# old_motor_line.net
KiCad netlist of a schematic drawn in EAGLE
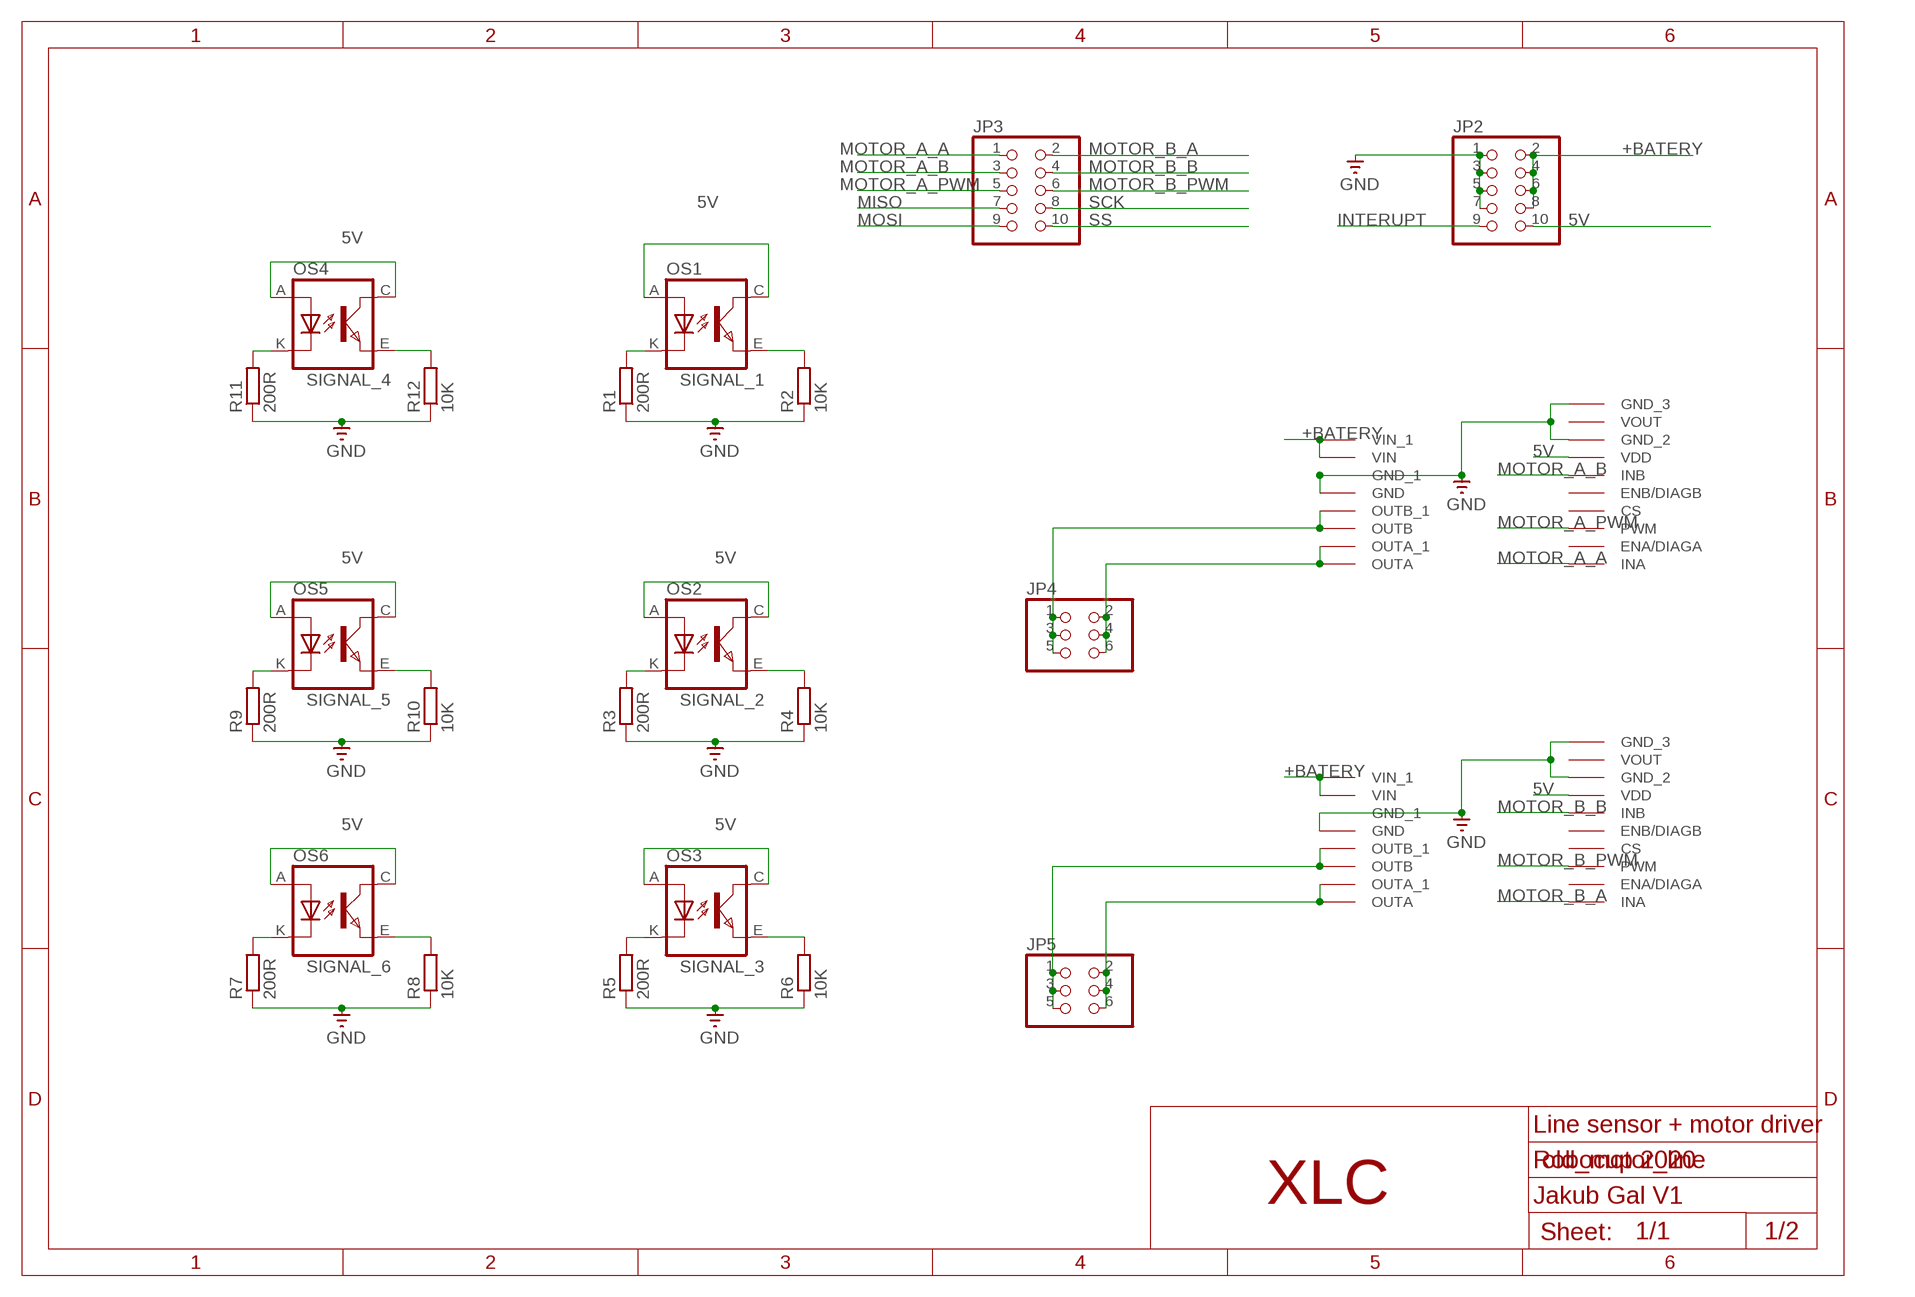
[diagram p0: schematic, sheet 1, part 1 of 2]
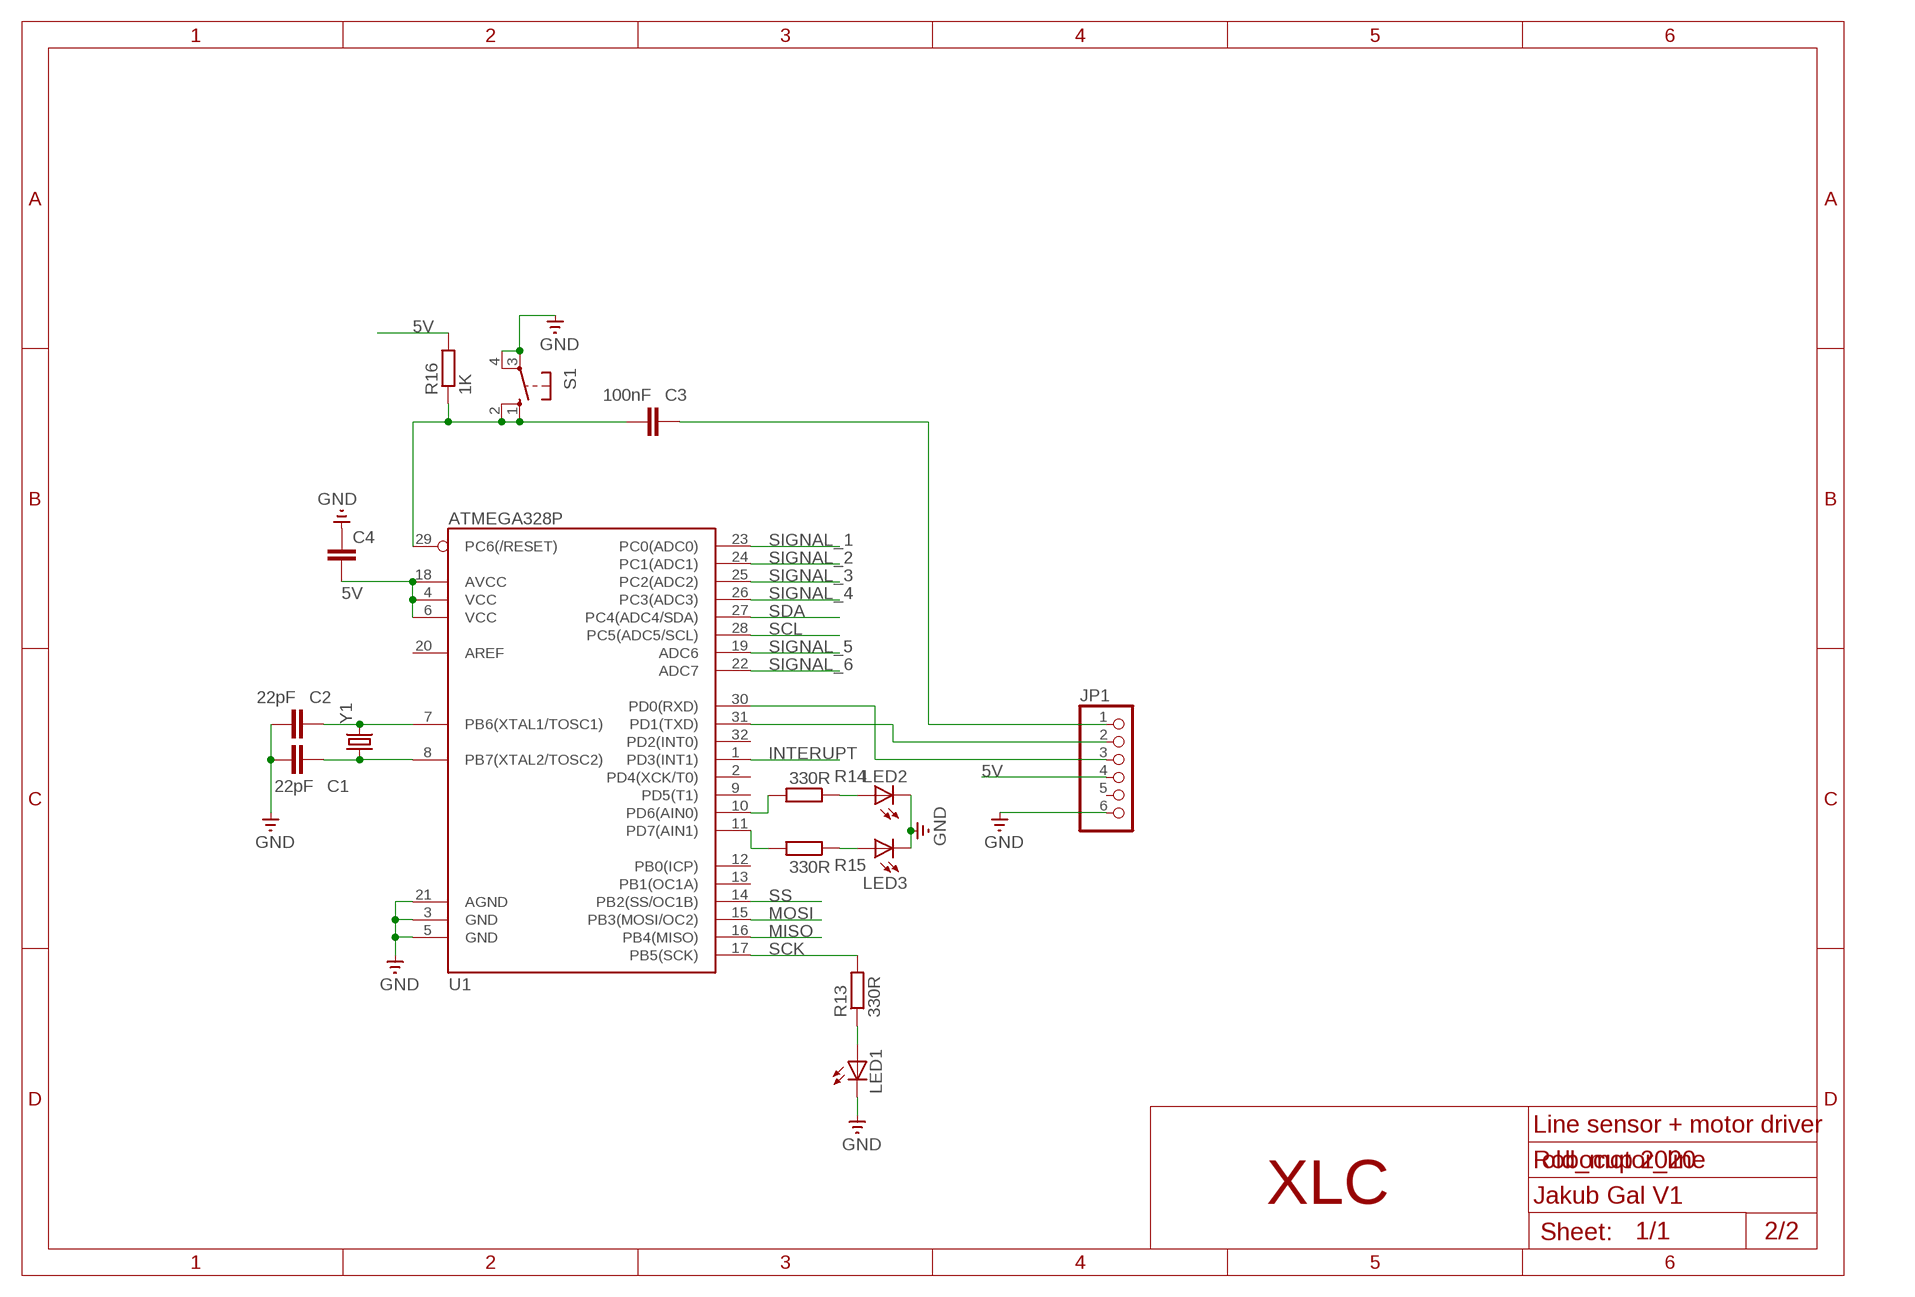
[diagram p1: schematic, sheet 1, part 2 of 2]

(export (version "E")
  (design (tool "Eeschema 10.0.6"))
  (components
    (comp (ref "C1")
      (value "22pF")
      (footprint "eagle-import:C0603")
      (libsource (lib "eagle-import") (part "rcl@1_C-EUC0603"))
    )
    (comp (ref "C2")
      (value "22pF")
      (footprint "eagle-import:C0603")
      (libsource (lib "eagle-import") (part "rcl@1_C-EUC0603"))
    )
    (comp (ref "C3")
      (value "100nF")
      (footprint "eagle-import:C0603")
      (libsource (lib "eagle-import") (part "rcl@1_C-EUC0603"))
    )
    (comp (ref "C4")
      (value "C-EUC0603")
      (footprint "eagle-import:C0603")
      (libsource (lib "eagle-import") (part "C-EUC0603"))
    )
    (comp (ref "JP1")
      (value "PINHD-1X6/90")
      (footprint "eagle-import:1X06_90")
      (libsource (lib "eagle-import") (part "PINHD-1X6/90"))
    )
    (comp (ref "JP2")
      (value "PINHD-2X5")
      (footprint "eagle-import:2X05")
      (libsource (lib "eagle-import") (part "PINHD-2X5"))
    )
    (comp (ref "JP3")
      (value "PINHD-2X5")
      (footprint "eagle-import:2X05")
      (libsource (lib "eagle-import") (part "PINHD-2X5"))
    )
    (comp (ref "JP4")
      (value "PINHD-2X3")
      (footprint "eagle-import:2X03")
      (libsource (lib "eagle-import") (part "PINHD-2X3"))
    )
    (comp (ref "JP5")
      (value "PINHD-2X3")
      (footprint "eagle-import:2X03")
      (libsource (lib "eagle-import") (part "PINHD-2X3"))
    )
    (comp (ref "LED1")
      (value "LEDCHIPLED_0603")
      (footprint "eagle-import:CHIPLED_0603")
      (libsource (lib "eagle-import") (part "LEDCHIPLED_0603"))
    )
    (comp (ref "LED2")
      (value "LEDCHIPLED_0603")
      (footprint "eagle-import:CHIPLED_0603")
      (libsource (lib "eagle-import") (part "LEDCHIPLED_0603"))
    )
    (comp (ref "LED3")
      (value "LEDCHIPLED_0603")
      (footprint "eagle-import:CHIPLED_0603")
      (libsource (lib "eagle-import") (part "LEDCHIPLED_0603"))
    )
    (comp (ref "OS1")
      (value "TCRT5000")
      (footprint "eagle-import:TCRT5000")
      (libsource (lib "eagle-import") (part "TCRT5000"))
    )
    (comp (ref "OS2")
      (value "TCRT5000")
      (footprint "eagle-import:TCRT5000")
      (libsource (lib "eagle-import") (part "TCRT5000"))
    )
    (comp (ref "OS3")
      (value "TCRT5000")
      (footprint "eagle-import:TCRT5000")
      (libsource (lib "eagle-import") (part "TCRT5000"))
    )
    (comp (ref "OS4")
      (value "TCRT5000")
      (footprint "eagle-import:TCRT5000")
      (fields (field (name "SPICEPREFIX") "O"))
      (libsource (lib "eagle-import") (part "TCRT5000"))
    )
    (comp (ref "OS5")
      (value "TCRT5000")
      (footprint "eagle-import:TCRT5000")
      (libsource (lib "eagle-import") (part "TCRT5000"))
    )
    (comp (ref "OS6")
      (value "TCRT5000")
      (footprint "eagle-import:TCRT5000")
      (fields (field (name "SPICEPREFIX") "O"))
      (libsource (lib "eagle-import") (part "TCRT5000"))
    )
    (comp (ref "R1")
      (value "200R")
      (footprint "eagle-import:R0603")
      (libsource (lib "eagle-import") (part "R-EU_R0603"))
    )
    (comp (ref "R2")
      (value "10K")
      (footprint "eagle-import:R0603")
      (libsource (lib "eagle-import") (part "R-EU_R0603"))
    )
    (comp (ref "R3")
      (value "200R")
      (footprint "eagle-import:R0603")
      (libsource (lib "eagle-import") (part "R-EU_R0603"))
    )
    (comp (ref "R4")
      (value "10K")
      (footprint "eagle-import:R0603")
      (libsource (lib "eagle-import") (part "R-EU_R0603"))
    )
    (comp (ref "R5")
      (value "200R")
      (footprint "eagle-import:R0603")
      (libsource (lib "eagle-import") (part "R-EU_R0603"))
    )
    (comp (ref "R6")
      (value "10K")
      (footprint "eagle-import:R0603")
      (libsource (lib "eagle-import") (part "R-EU_R0603"))
    )
    (comp (ref "R7")
      (value "200R")
      (footprint "eagle-import:R0603")
      (libsource (lib "eagle-import") (part "R-EU_R0603"))
    )
    (comp (ref "R8")
      (value "10K")
      (footprint "eagle-import:R0603")
      (libsource (lib "eagle-import") (part "R-EU_R0603"))
    )
    (comp (ref "R9")
      (value "200R")
      (footprint "eagle-import:R0603")
      (libsource (lib "eagle-import") (part "R-EU_R0603"))
    )
    (comp (ref "R10")
      (value "10K")
      (footprint "eagle-import:R0603")
      (libsource (lib "eagle-import") (part "R-EU_R0603"))
    )
    (comp (ref "R11")
      (value "200R")
      (footprint "eagle-import:R0603")
      (libsource (lib "eagle-import") (part "R-EU_R0603"))
    )
    (comp (ref "R12")
      (value "10K")
      (footprint "eagle-import:R0603")
      (libsource (lib "eagle-import") (part "R-EU_R0603"))
    )
    (comp (ref "R13")
      (value "330R")
      (footprint "eagle-import:R0603")
      (libsource (lib "eagle-import") (part "R-EU_R0603"))
    )
    (comp (ref "R14")
      (value "330R")
      (footprint "eagle-import:R0603")
      (libsource (lib "eagle-import") (part "R-EU_R0603"))
    )
    (comp (ref "R15")
      (value "330R")
      (footprint "eagle-import:R0603")
      (libsource (lib "eagle-import") (part "R-EU_R0603"))
    )
    (comp (ref "R16")
      (value "1K")
      (footprint "eagle-import:R0603")
      (libsource (lib "eagle-import") (part "R-EU_R0603"))
    )
    (comp (ref "S1")
      (value "10-XX")
      (footprint "eagle-import:B3F-10XX")
      (fields (field (name "MPN") "B3F-1000"))
      (libsource (lib "eagle-import") (part "10-XX"))
    )
    (comp (ref "U$1")
      (value "MOTOR_DRIVER")
      (footprint "eagle-import:MOTOR_DRIVER")
      (libsource (lib "eagle-import") (part "MOTOR_DRIVER"))
    )
    (comp (ref "U$2")
      (value "MOTOR_DRIVER")
      (footprint "eagle-import:MOTOR_DRIVER")
      (libsource (lib "eagle-import") (part "MOTOR_DRIVER"))
    )
    (comp (ref "U1")
      (value "ATMEGA328P")
      (footprint "eagle-import:TQFP32-08")
      (libsource (lib "eagle-import") (part "ATMEGA328_SMT"))
    )
    (comp (ref "Y1")
      (value "CRYSTALHC49US")
      (footprint "eagle-import:HC49US")
      (libsource (lib "eagle-import") (part "CRYSTALHC49US"))
    )
  )
  (nets
    (net (code "1") (name "/+BATERY") (class "Default")
      (node (ref "JP2") (pin "2") (pinfunction "2_2") (pintype "passive"))
      (node (ref "JP2") (pin "4") (pinfunction "4_4") (pintype "passive"))
      (node (ref "JP2") (pin "6") (pinfunction "6_6") (pintype "passive"))
      (node (ref "JP2") (pin "8") (pinfunction "8_8") (pintype "passive"))
      (node (ref "U$1") (pin "VIN") (pinfunction "VIN_VIN") (pintype "bidirectional"))
      (node (ref "U$1") (pin "VIN_1") (pinfunction "VIN_1_VIN_1") (pintype "bidirectional"))
      (node (ref "U$2") (pin "VIN") (pinfunction "VIN_VIN") (pintype "bidirectional"))
      (node (ref "U$2") (pin "VIN_1") (pinfunction "VIN_1_VIN_1") (pintype "bidirectional"))
    )
    (net (code "2") (name "/5V") (class "Default")
      (node (ref "C4") (pin "2") (pinfunction "2_2") (pintype "passive"))
      (node (ref "JP1") (pin "4") (pinfunction "4_4") (pintype "passive"))
      (node (ref "JP2") (pin "10") (pinfunction "10_10") (pintype "passive"))
      (node (ref "OS1") (pin "A") (pinfunction "ANODE_A") (pintype "passive"))
      (node (ref "OS1") (pin "C") (pinfunction "COLLECTOR_C") (pintype "passive"))
      (node (ref "OS2") (pin "A") (pinfunction "ANODE_A") (pintype "passive"))
      (node (ref "OS2") (pin "C") (pinfunction "COLLECTOR_C") (pintype "passive"))
      (node (ref "OS3") (pin "A") (pinfunction "ANODE_A") (pintype "passive"))
      (node (ref "OS3") (pin "C") (pinfunction "COLLECTOR_C") (pintype "passive"))
      (node (ref "OS4") (pin "A") (pinfunction "ANODE_A") (pintype "passive"))
      (node (ref "OS4") (pin "C") (pinfunction "COLLECTOR_C") (pintype "passive"))
      (node (ref "OS5") (pin "A") (pinfunction "ANODE_A") (pintype "passive"))
      (node (ref "OS5") (pin "C") (pinfunction "COLLECTOR_C") (pintype "passive"))
      (node (ref "OS6") (pin "A") (pinfunction "ANODE_A") (pintype "passive"))
      (node (ref "OS6") (pin "C") (pinfunction "COLLECTOR_C") (pintype "passive"))
      (node (ref "R16") (pin "2") (pinfunction "2_2") (pintype "passive"))
      (node (ref "U$1") (pin "VDD") (pinfunction "VDD_VDD") (pintype "bidirectional"))
      (node (ref "U$2") (pin "VDD") (pinfunction "VDD_VDD") (pintype "bidirectional"))
      (node (ref "U1") (pin "18") (pinfunction "AVCC_18") (pintype "bidirectional"))
      (node (ref "U1") (pin "4") (pinfunction "VCC_4") (pintype "bidirectional"))
      (node (ref "U1") (pin "6") (pinfunction "VCC_6") (pintype "bidirectional"))
    )
    (net (code "3") (name "/INTERUPT") (class "Default")
      (node (ref "JP2") (pin "9") (pinfunction "9_9") (pintype "passive"))
      (node (ref "U1") (pin "1") (pinfunction "PD3(INT1)_1") (pintype "bidirectional"))
    )
    (net (code "4") (name "/MISO") (class "Default")
      (node (ref "JP3") (pin "7") (pinfunction "7_7") (pintype "passive"))
      (node (ref "U1") (pin "16") (pinfunction "PB4(MISO)_16") (pintype "bidirectional"))
    )
    (net (code "5") (name "/MOSI") (class "Default")
      (node (ref "JP3") (pin "9") (pinfunction "9_9") (pintype "passive"))
      (node (ref "U1") (pin "15") (pinfunction "PB3(MOSI/OC2)_15") (pintype "bidirectional"))
    )
    (net (code "6") (name "/MOTOR_A_A") (class "Default")
      (node (ref "JP3") (pin "1") (pinfunction "1_1") (pintype "passive"))
      (node (ref "U$1") (pin "INA") (pinfunction "INA_INA") (pintype "bidirectional"))
    )
    (net (code "7") (name "/MOTOR_A_B") (class "Default")
      (node (ref "JP3") (pin "3") (pinfunction "3_3") (pintype "passive"))
      (node (ref "U$1") (pin "INB") (pinfunction "INB_INB") (pintype "bidirectional"))
    )
    (net (code "8") (name "/MOTOR_A_PWM") (class "Default")
      (node (ref "JP3") (pin "5") (pinfunction "5_5") (pintype "passive"))
      (node (ref "U$1") (pin "PWM") (pinfunction "PWM_PWM") (pintype "bidirectional"))
    )
    (net (code "9") (name "/MOTOR_B_A") (class "Default")
      (node (ref "JP3") (pin "2") (pinfunction "2_2") (pintype "passive"))
      (node (ref "U$2") (pin "INA") (pinfunction "INA_INA") (pintype "bidirectional"))
    )
    (net (code "10") (name "/MOTOR_B_B") (class "Default")
      (node (ref "JP3") (pin "4") (pinfunction "4_4") (pintype "passive"))
      (node (ref "U$2") (pin "INB") (pinfunction "INB_INB") (pintype "bidirectional"))
    )
    (net (code "11") (name "/MOTOR_B_PWM") (class "Default")
      (node (ref "JP3") (pin "6") (pinfunction "6_6") (pintype "passive"))
      (node (ref "U$2") (pin "PWM") (pinfunction "PWM_PWM") (pintype "bidirectional"))
    )
    (net (code "12") (name "/SCK") (class "Default")
      (node (ref "JP3") (pin "8") (pinfunction "8_8") (pintype "passive"))
      (node (ref "R13") (pin "2") (pinfunction "2_2") (pintype "passive"))
      (node (ref "U1") (pin "17") (pinfunction "PB5(SCK)_17") (pintype "bidirectional"))
    )
    (net (code "13") (name "/SCL") (class "Default")
      (node (ref "U1") (pin "28") (pinfunction "PC5(ADC5/SCL)_28") (pintype "bidirectional"))
    )
    (net (code "14") (name "/SDA") (class "Default")
      (node (ref "U1") (pin "27") (pinfunction "PC4(ADC4/SDA)_27") (pintype "bidirectional"))
    )
    (net (code "15") (name "/SIGNAL_1") (class "Default")
      (node (ref "OS1") (pin "E") (pinfunction "EMITTER_E") (pintype "passive"))
      (node (ref "R2") (pin "2") (pinfunction "2_2") (pintype "passive"))
      (node (ref "U1") (pin "23") (pinfunction "PC0(ADC0)_23") (pintype "bidirectional"))
    )
    (net (code "16") (name "/SIGNAL_2") (class "Default")
      (node (ref "OS2") (pin "E") (pinfunction "EMITTER_E") (pintype "passive"))
      (node (ref "R4") (pin "2") (pinfunction "2_2") (pintype "passive"))
      (node (ref "U1") (pin "24") (pinfunction "PC1(ADC1)_24") (pintype "bidirectional"))
    )
    (net (code "17") (name "/SIGNAL_3") (class "Default")
      (node (ref "OS3") (pin "E") (pinfunction "EMITTER_E") (pintype "passive"))
      (node (ref "R6") (pin "2") (pinfunction "2_2") (pintype "passive"))
      (node (ref "U1") (pin "25") (pinfunction "PC2(ADC2)_25") (pintype "bidirectional"))
    )
    (net (code "18") (name "/SIGNAL_4") (class "Default")
      (node (ref "OS4") (pin "E") (pinfunction "EMITTER_E") (pintype "passive"))
      (node (ref "R12") (pin "2") (pinfunction "2_2") (pintype "passive"))
      (node (ref "U1") (pin "26") (pinfunction "PC3(ADC3)_26") (pintype "bidirectional"))
    )
    (net (code "19") (name "/SIGNAL_5") (class "Default")
      (node (ref "OS5") (pin "E") (pinfunction "EMITTER_E") (pintype "passive"))
      (node (ref "R10") (pin "2") (pinfunction "2_2") (pintype "passive"))
      (node (ref "U1") (pin "19") (pinfunction "ADC6_19") (pintype "bidirectional"))
    )
    (net (code "20") (name "/SIGNAL_6") (class "Default")
      (node (ref "OS6") (pin "E") (pinfunction "EMITTER_E") (pintype "passive"))
      (node (ref "R8") (pin "2") (pinfunction "2_2") (pintype "passive"))
      (node (ref "U1") (pin "22") (pinfunction "ADC7_22") (pintype "bidirectional"))
    )
    (net (code "21") (name "/SS") (class "Default")
      (node (ref "JP3") (pin "10") (pinfunction "10_10") (pintype "passive"))
      (node (ref "U1") (pin "14") (pinfunction "PB2(SS/OC1B)_14") (pintype "bidirectional"))
    )
    (net (code "22") (name "GND") (class "Default")
      (node (ref "C1") (pin "1") (pinfunction "1_1") (pintype "passive"))
      (node (ref "C2") (pin "1") (pinfunction "1_1") (pintype "passive"))
      (node (ref "C4") (pin "1") (pinfunction "1_1") (pintype "passive"))
      (node (ref "JP1") (pin "6") (pinfunction "6_6") (pintype "passive"))
      (node (ref "JP2") (pin "1") (pinfunction "1_1") (pintype "passive"))
      (node (ref "JP2") (pin "3") (pinfunction "3_3") (pintype "passive"))
      (node (ref "JP2") (pin "5") (pinfunction "5_5") (pintype "passive"))
      (node (ref "JP2") (pin "7") (pinfunction "7_7") (pintype "passive"))
      (node (ref "LED1") (pin "C") (pinfunction "C_C") (pintype "passive"))
      (node (ref "LED2") (pin "C") (pinfunction "C_C") (pintype "passive"))
      (node (ref "LED3") (pin "C") (pinfunction "C_C") (pintype "passive"))
      (node (ref "R1") (pin "1") (pinfunction "1_1") (pintype "passive"))
      (node (ref "R10") (pin "1") (pinfunction "1_1") (pintype "passive"))
      (node (ref "R11") (pin "1") (pinfunction "1_1") (pintype "passive"))
      (node (ref "R12") (pin "1") (pinfunction "1_1") (pintype "passive"))
      (node (ref "R2") (pin "1") (pinfunction "1_1") (pintype "passive"))
      (node (ref "R3") (pin "1") (pinfunction "1_1") (pintype "passive"))
      (node (ref "R4") (pin "1") (pinfunction "1_1") (pintype "passive"))
      (node (ref "R5") (pin "1") (pinfunction "1_1") (pintype "passive"))
      (node (ref "R6") (pin "1") (pinfunction "1_1") (pintype "passive"))
      (node (ref "R7") (pin "1") (pinfunction "1_1") (pintype "passive"))
      (node (ref "R8") (pin "1") (pinfunction "1_1") (pintype "passive"))
      (node (ref "R9") (pin "1") (pinfunction "1_1") (pintype "passive"))
      (node (ref "S1") (pin "3") (pinfunction "P_3") (pintype "passive"))
      (node (ref "S1") (pin "4") (pinfunction "P1_4") (pintype "passive"))
      (node (ref "U$1") (pin "GND") (pinfunction "GND_GND") (pintype "bidirectional"))
      (node (ref "U$1") (pin "GND_1") (pinfunction "GND_1_GND_1") (pintype "bidirectional"))
      (node (ref "U$1") (pin "GND_2") (pinfunction "GND_2_GND_2") (pintype "bidirectional"))
      (node (ref "U$1") (pin "GND_3") (pinfunction "GND_3_GND_3") (pintype "bidirectional"))
      (node (ref "U$2") (pin "GND") (pinfunction "GND_GND") (pintype "bidirectional"))
      (node (ref "U$2") (pin "GND_1") (pinfunction "GND_1_GND_1") (pintype "bidirectional"))
      (node (ref "U$2") (pin "GND_2") (pinfunction "GND_2_GND_2") (pintype "bidirectional"))
      (node (ref "U$2") (pin "GND_3") (pinfunction "GND_3_GND_3") (pintype "bidirectional"))
      (node (ref "U1") (pin "21") (pinfunction "AGND_21") (pintype "bidirectional"))
      (node (ref "U1") (pin "3") (pinfunction "GND_3") (pintype "bidirectional"))
      (node (ref "U1") (pin "5") (pinfunction "GND_5") (pintype "bidirectional"))
    )
    (net (code "23") (name "Net-(C3-Pad2)") (class "Default")
      (node (ref "C3") (pin "2") (pinfunction "2_2") (pintype "passive"))
      (node (ref "JP1") (pin "1") (pinfunction "1_1") (pintype "passive"))
    )
    (net (code "24") (name "Net-(JP4-Pad1)") (class "Default")
      (node (ref "JP4") (pin "1") (pinfunction "1_1") (pintype "passive"))
      (node (ref "JP4") (pin "3") (pinfunction "3_3") (pintype "passive"))
      (node (ref "JP4") (pin "5") (pinfunction "5_5") (pintype "passive"))
      (node (ref "U$1") (pin "OUTB") (pinfunction "OUTB_OUTB") (pintype "bidirectional"))
      (node (ref "U$1") (pin "OUTB_1") (pinfunction "OUTB_1_OUTB_1") (pintype "bidirectional"))
    )
    (net (code "25") (name "Net-(JP4-Pad2)") (class "Default")
      (node (ref "JP4") (pin "2") (pinfunction "2_2") (pintype "passive"))
      (node (ref "JP4") (pin "4") (pinfunction "4_4") (pintype "passive"))
      (node (ref "JP4") (pin "6") (pinfunction "6_6") (pintype "passive"))
      (node (ref "U$1") (pin "OUTA") (pinfunction "OUTA_OUTA") (pintype "bidirectional"))
      (node (ref "U$1") (pin "OUTA_1") (pinfunction "OUTA_1_OUTA_1") (pintype "bidirectional"))
    )
    (net (code "26") (name "Net-(JP5-Pad1)") (class "Default")
      (node (ref "JP5") (pin "1") (pinfunction "1_1") (pintype "passive"))
      (node (ref "JP5") (pin "3") (pinfunction "3_3") (pintype "passive"))
      (node (ref "JP5") (pin "5") (pinfunction "5_5") (pintype "passive"))
      (node (ref "U$2") (pin "OUTB") (pinfunction "OUTB_OUTB") (pintype "bidirectional"))
      (node (ref "U$2") (pin "OUTB_1") (pinfunction "OUTB_1_OUTB_1") (pintype "bidirectional"))
    )
    (net (code "27") (name "Net-(JP5-Pad2)") (class "Default")
      (node (ref "JP5") (pin "2") (pinfunction "2_2") (pintype "passive"))
      (node (ref "JP5") (pin "4") (pinfunction "4_4") (pintype "passive"))
      (node (ref "JP5") (pin "6") (pinfunction "6_6") (pintype "passive"))
      (node (ref "U$2") (pin "OUTA") (pinfunction "OUTA_OUTA") (pintype "bidirectional"))
      (node (ref "U$2") (pin "OUTA_1") (pinfunction "OUTA_1_OUTA_1") (pintype "bidirectional"))
    )
    (net (code "28") (name "Net-(LED1-PadA)") (class "Default")
      (node (ref "LED1") (pin "A") (pinfunction "A_A") (pintype "passive"))
      (node (ref "R13") (pin "1") (pinfunction "1_1") (pintype "passive"))
    )
    (net (code "29") (name "Net-(LED2-PadA)") (class "Default")
      (node (ref "LED2") (pin "A") (pinfunction "A_A") (pintype "passive"))
      (node (ref "R14") (pin "1") (pinfunction "1_1") (pintype "passive"))
    )
    (net (code "30") (name "Net-(LED3-PadA)") (class "Default")
      (node (ref "LED3") (pin "A") (pinfunction "A_A") (pintype "passive"))
      (node (ref "R15") (pin "1") (pinfunction "1_1") (pintype "passive"))
    )
    (net (code "31") (name "Net-(OS1-CATHODE)") (class "Default")
      (node (ref "OS1") (pin "K") (pinfunction "CATHODE_K") (pintype "passive"))
      (node (ref "R1") (pin "2") (pinfunction "2_2") (pintype "passive"))
    )
    (net (code "32") (name "Net-(OS2-CATHODE)") (class "Default")
      (node (ref "OS2") (pin "K") (pinfunction "CATHODE_K") (pintype "passive"))
      (node (ref "R3") (pin "2") (pinfunction "2_2") (pintype "passive"))
    )
    (net (code "33") (name "Net-(OS3-CATHODE)") (class "Default")
      (node (ref "OS3") (pin "K") (pinfunction "CATHODE_K") (pintype "passive"))
      (node (ref "R5") (pin "2") (pinfunction "2_2") (pintype "passive"))
    )
    (net (code "34") (name "Net-(OS4-CATHODE)") (class "Default")
      (node (ref "OS4") (pin "K") (pinfunction "CATHODE_K") (pintype "passive"))
      (node (ref "R11") (pin "2") (pinfunction "2_2") (pintype "passive"))
    )
    (net (code "35") (name "Net-(OS5-CATHODE)") (class "Default")
      (node (ref "OS5") (pin "K") (pinfunction "CATHODE_K") (pintype "passive"))
      (node (ref "R9") (pin "2") (pinfunction "2_2") (pintype "passive"))
    )
    (net (code "36") (name "Net-(OS6-CATHODE)") (class "Default")
      (node (ref "OS6") (pin "K") (pinfunction "CATHODE_K") (pintype "passive"))
      (node (ref "R7") (pin "2") (pinfunction "2_2") (pintype "passive"))
    )
    (net (code "37") (name "Net-(S1-S)") (class "Default")
      (node (ref "C3") (pin "1") (pinfunction "1_1") (pintype "passive"))
      (node (ref "R16") (pin "1") (pinfunction "1_1") (pintype "passive"))
      (node (ref "S1") (pin "1") (pinfunction "S_1") (pintype "passive"))
      (node (ref "S1") (pin "2") (pinfunction "S1_2") (pintype "passive"))
      (node (ref "U1") (pin "29") (pinfunction "PC6(/RESET)_29") (pintype "bidirectional"))
    )
    (net (code "38") (name "Net-(U1-PB6(XTAL1{slash}TOSC1))") (class "Default")
      (node (ref "C2") (pin "2") (pinfunction "2_2") (pintype "passive"))
      (node (ref "U1") (pin "7") (pinfunction "PB6(XTAL1/TOSC1)_7") (pintype "bidirectional"))
      (node (ref "Y1") (pin "2") (pinfunction "2_2") (pintype "passive"))
    )
    (net (code "39") (name "Net-(U1-PB7(XTAL2{slash}TOSC2))") (class "Default")
      (node (ref "C1") (pin "2") (pinfunction "2_2") (pintype "passive"))
      (node (ref "U1") (pin "8") (pinfunction "PB7(XTAL2/TOSC2)_8") (pintype "bidirectional"))
      (node (ref "Y1") (pin "1") (pinfunction "1_1") (pintype "passive"))
    )
    (net (code "40") (name "Net-(U1-PD0(RXD))") (class "Default")
      (node (ref "JP1") (pin "3") (pinfunction "3_3") (pintype "passive"))
      (node (ref "U1") (pin "30") (pinfunction "PD0(RXD)_30") (pintype "bidirectional"))
    )
    (net (code "41") (name "Net-(U1-PD1(TXD))") (class "Default")
      (node (ref "JP1") (pin "2") (pinfunction "2_2") (pintype "passive"))
      (node (ref "U1") (pin "31") (pinfunction "PD1(TXD)_31") (pintype "bidirectional"))
    )
    (net (code "42") (name "Net-(U1-PD6(AIN0))") (class "Default")
      (node (ref "R14") (pin "2") (pinfunction "2_2") (pintype "passive"))
      (node (ref "U1") (pin "10") (pinfunction "PD6(AIN0)_10") (pintype "bidirectional"))
    )
    (net (code "43") (name "Net-(U1-PD7(AIN1))") (class "Default")
      (node (ref "R15") (pin "2") (pinfunction "2_2") (pintype "passive"))
      (node (ref "U1") (pin "11") (pinfunction "PD7(AIN1)_11") (pintype "bidirectional"))
    )
    (net (code "44") (name "unconnected-(JP1-Pad5)") (class "Default")
      (node (ref "JP1") (pin "5") (pinfunction "5_5") (pintype "passive"))
    )
    (net (code "45") (name "unconnected-(U$1-PadCS)") (class "Default")
      (node (ref "U$1") (pin "CS") (pinfunction "CS_CS") (pintype "bidirectional"))
    )
    (net (code "46") (name "unconnected-(U$1-PadENA{slash}DIAGA)") (class "Default")
      (node (ref "U$1") (pin "ENA/DIAGA") (pinfunction "ENA/DIAGA_ENA/DIAGA") (pintype "bidirectional"))
    )
    (net (code "47") (name "unconnected-(U$1-PadENB{slash}DIAGB)") (class "Default")
      (node (ref "U$1") (pin "ENB/DIAGB") (pinfunction "ENB/DIAGB_ENB/DIAGB") (pintype "bidirectional"))
    )
    (net (code "48") (name "unconnected-(U$1-PadVOUT)") (class "Default")
      (node (ref "U$1") (pin "VOUT") (pinfunction "VOUT_VOUT") (pintype "bidirectional"))
    )
    (net (code "49") (name "unconnected-(U$2-PadCS)") (class "Default")
      (node (ref "U$2") (pin "CS") (pinfunction "CS_CS") (pintype "bidirectional"))
    )
    (net (code "50") (name "unconnected-(U$2-PadENA{slash}DIAGA)") (class "Default")
      (node (ref "U$2") (pin "ENA/DIAGA") (pinfunction "ENA/DIAGA_ENA/DIAGA") (pintype "bidirectional"))
    )
    (net (code "51") (name "unconnected-(U$2-PadENB{slash}DIAGB)") (class "Default")
      (node (ref "U$2") (pin "ENB/DIAGB") (pinfunction "ENB/DIAGB_ENB/DIAGB") (pintype "bidirectional"))
    )
    (net (code "52") (name "unconnected-(U$2-PadVOUT)") (class "Default")
      (node (ref "U$2") (pin "VOUT") (pinfunction "VOUT_VOUT") (pintype "bidirectional"))
    )
    (net (code "53") (name "unconnected-(U1-AREF-Pad20)") (class "Default")
      (node (ref "U1") (pin "20") (pinfunction "AREF_20") (pintype "bidirectional"))
    )
    (net (code "54") (name "unconnected-(U1-PB0(ICP)-Pad12)") (class "Default")
      (node (ref "U1") (pin "12") (pinfunction "PB0(ICP)_12") (pintype "bidirectional"))
    )
    (net (code "55") (name "unconnected-(U1-PB1(OC1A)-Pad13)") (class "Default")
      (node (ref "U1") (pin "13") (pinfunction "PB1(OC1A)_13") (pintype "bidirectional"))
    )
    (net (code "56") (name "unconnected-(U1-PD2(INT0)-Pad32)") (class "Default")
      (node (ref "U1") (pin "32") (pinfunction "PD2(INT0)_32") (pintype "bidirectional"))
    )
    (net (code "57") (name "unconnected-(U1-PD4(XCK{slash}T0)-Pad2)") (class "Default")
      (node (ref "U1") (pin "2") (pinfunction "PD4(XCK/T0)_2") (pintype "bidirectional"))
    )
    (net (code "58") (name "unconnected-(U1-PD5(T1)-Pad9)") (class "Default")
      (node (ref "U1") (pin "9") (pinfunction "PD5(T1)_9") (pintype "bidirectional"))
    )
  )
)
